# MD5133-A02-01.net
KiCad netlist of a schematic drawn in Altium Designer
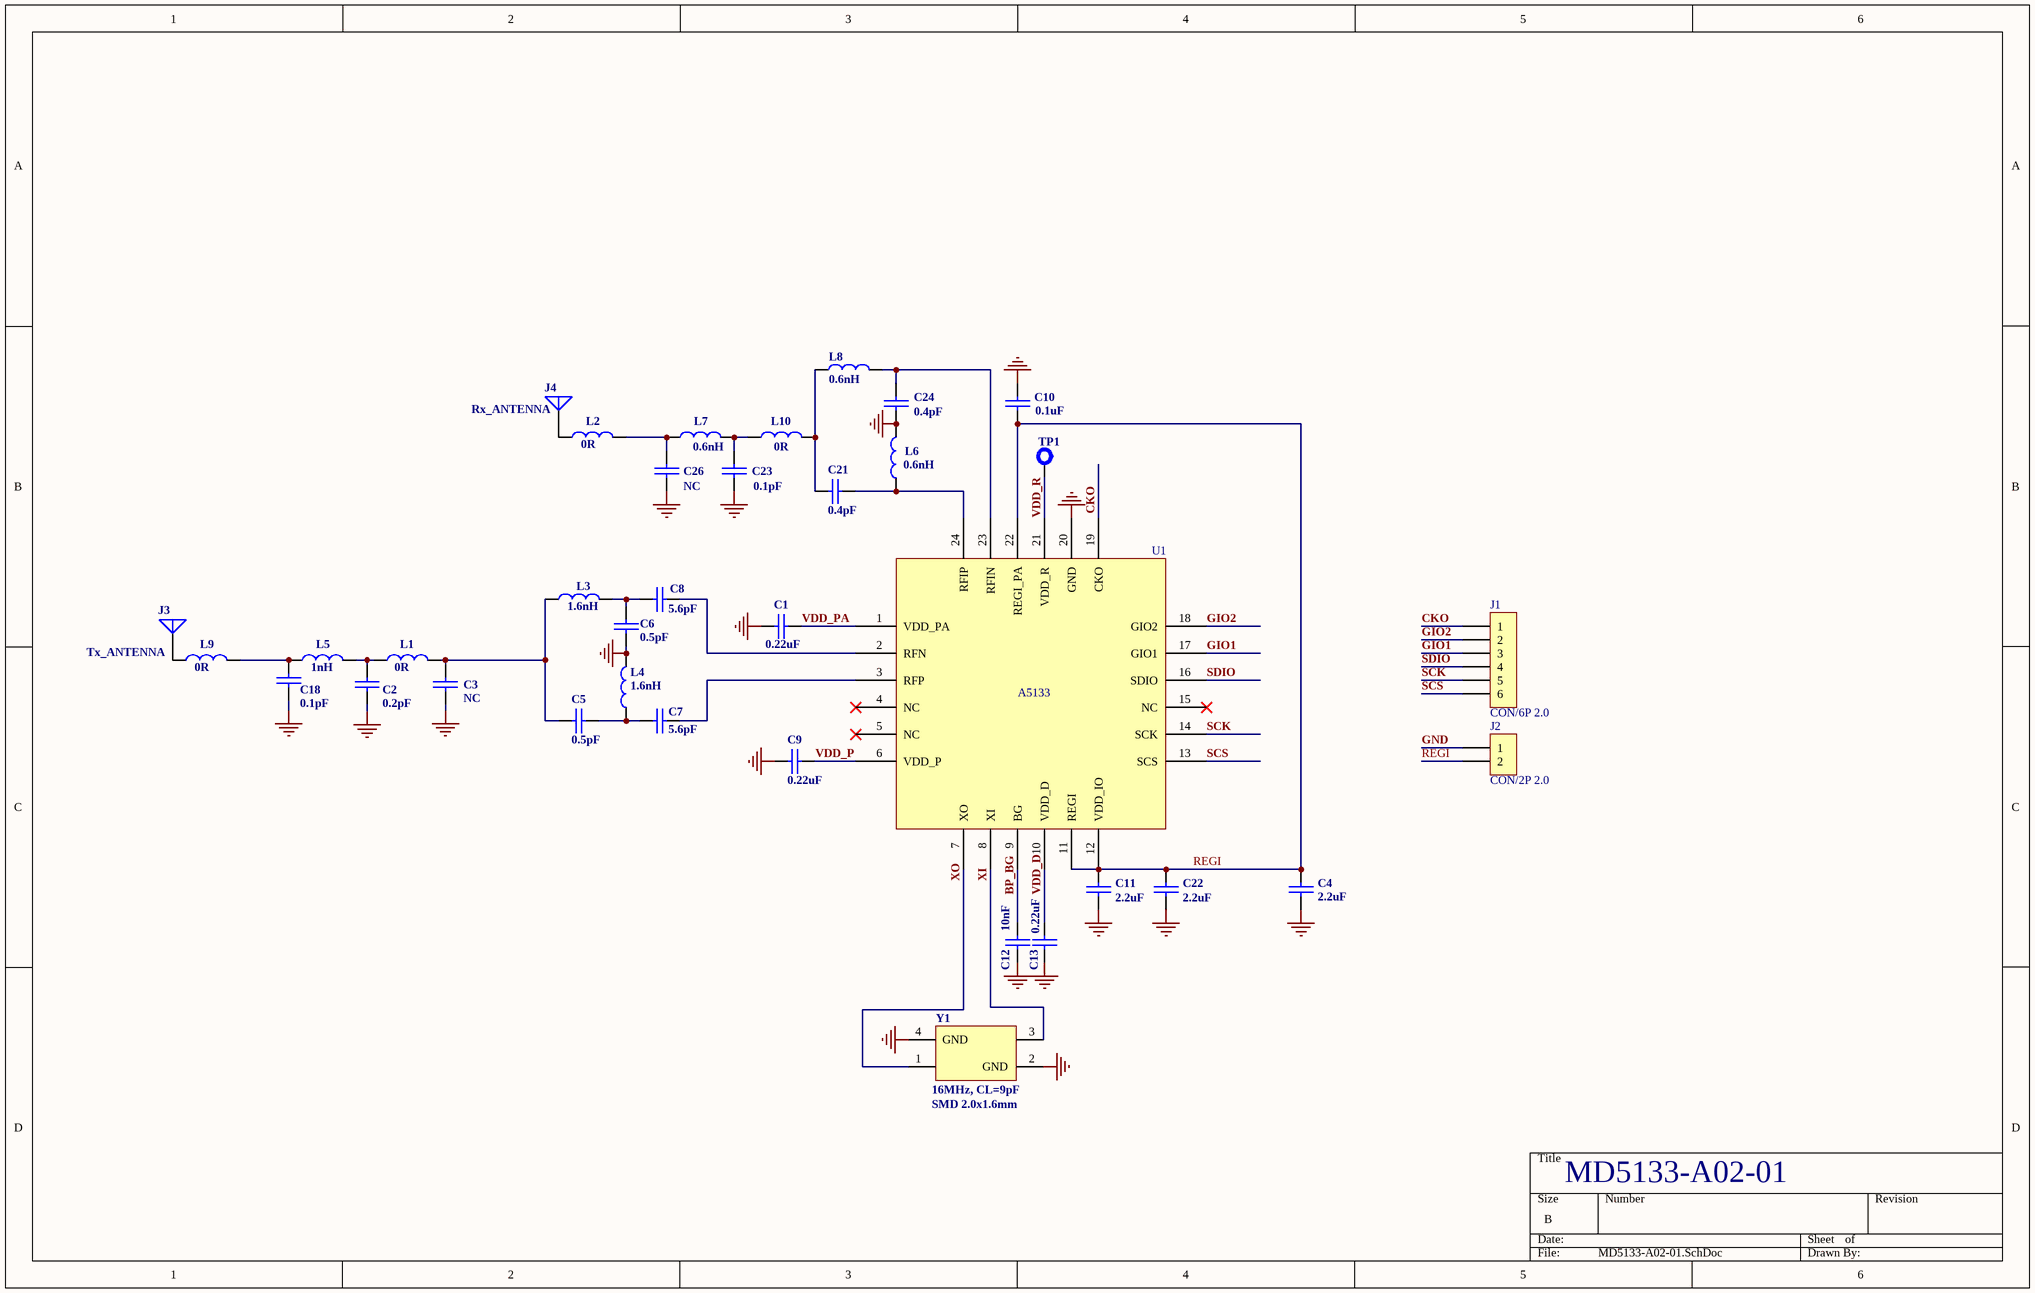
[diagram p0: MD5133-A02-01.SchDoc]

(export (version "E")
  (design (tool "Eeschema 10.0.6"))
  (components
    (comp (ref "C1") (value "0.22uF") (footprint "0402") (libsource (lib "*") (part "CAP")))
    (comp (ref "C2")
      (value "0.2pF")
      (footprint "0402-3")
      (description "Chip C")
      (libsource (lib "*") (part "C/0603"))
    )
    (comp (ref "C3")
      (value "NC")
      (footprint "0402-3")
      (description "Chip C")
      (libsource (lib "*") (part "C/0603"))
    )
    (comp (ref "C4") (value "2.2uF") (footprint "0402") (libsource (lib "*") (part "CAP")))
    (comp (ref "C5")
      (value "0.5pF")
      (footprint "0402-3")
      (description "Chip C")
      (libsource (lib "*") (part "C/0603"))
    )
    (comp (ref "C6")
      (value "0.5pF")
      (footprint "0402-3")
      (description "Chip C")
      (libsource (lib "*") (part "C/0603"))
    )
    (comp (ref "C7")
      (value "5.6pF")
      (footprint "0402-3")
      (description "Chip C")
      (libsource (lib "*") (part "C/0603"))
    )
    (comp (ref "C8")
      (value "5.6pF")
      (footprint "0402-3")
      (description "Chip C")
      (libsource (lib "*") (part "C/0603"))
    )
    (comp (ref "C9") (value "0.22uF") (footprint "0402") (libsource (lib "*") (part "CAP")))
    (comp (ref "C10")
      (value "0.1uF")
      (footprint "0402")
      (description "Chip C")
      (libsource (lib "*") (part "C/0603"))
    )
    (comp (ref "C11") (value "2.2uF") (footprint "0402") (libsource (lib "*") (part "CAP")))
    (comp (ref "C12") (value "10nF") (footprint "0402") (libsource (lib "*") (part "CAP")))
    (comp (ref "C13") (value "0.22uF") (footprint "0402") (libsource (lib "*") (part "CAP")))
    (comp (ref "C18")
      (value "0.1pF")
      (footprint "0402-3")
      (description "Chip C")
      (libsource (lib "*") (part "C/0603"))
    )
    (comp (ref "C21")
      (value "0.4pF")
      (footprint "0402-3")
      (description "Chip C")
      (libsource (lib "*") (part "C/0603"))
    )
    (comp (ref "C22") (value "2.2uF") (footprint "0402") (libsource (lib "*") (part "CAP")))
    (comp (ref "C23")
      (value "0.1pF")
      (footprint "0402-3")
      (description "Chip C")
      (libsource (lib "*") (part "C/0603"))
    )
    (comp (ref "C24")
      (value "0.4pF")
      (footprint "0402-3")
      (description "Chip C")
      (libsource (lib "*") (part "C/0603"))
    )
    (comp (ref "C26")
      (value "NC")
      (footprint "0402-3")
      (description "Chip C")
      (libsource (lib "*") (part "C/0603"))
    )
    (comp (ref "J1")
      (value "CON/6P 2.0")
      (footprint "HDR6_2.0")
      (description "Hole 36mil")
      (libsource (lib "AMICCOM-S") (part "CON/6P 2.0"))
    )
    (comp (ref "J2")
      (value "CON/2P 2.0")
      (footprint "HDR2_2.0")
      (description "Hole 36mil")
      (libsource (lib "AMICCOM-S") (part "CON/2P 2.0"))
    )
    (comp (ref "J3")
      (value "Tx_ANTENNA")
      (footprint "ANT3_5.8G-A1011")
      (libsource (lib "AMICCOM-S") (part "ANTENNA"))
    )
    (comp (ref "J4")
      (value "Rx_ANTENNA")
      (footprint "ANT3_5.8G-A1011")
      (libsource (lib "AMICCOM-S") (part "ANTENNA"))
    )
    (comp (ref "L1") (value "0R") (footprint "0402-3") (libsource (lib "") (part "L/0603_4")))
    (comp (ref "L2") (value "0R") (footprint "0402-3") (libsource (lib "") (part "L/0603_3")))
    (comp (ref "L3") (value "1.6nH") (footprint "0402-3") (libsource (lib "") (part "L/0603_4")))
    (comp (ref "L4") (value "1.6nH") (footprint "0402-3") (libsource (lib "") (part "L/0603_2")))
    (comp (ref "L5") (value "1nH") (footprint "0402-3") (libsource (lib "") (part "L/0603_3")))
    (comp (ref "L6") (value "0.6nH") (footprint "0402-3") (libsource (lib "") (part "L/0603_1")))
    (comp (ref "L7") (value "0.6nH") (footprint "0402-3") (libsource (lib "*") (part "L/0603")))
    (comp (ref "L8") (value "0.6nH") (footprint "0402-3") (libsource (lib "*") (part "L/0603")))
    (comp (ref "L9") (value "0R") (footprint "0402-3") (libsource (lib "") (part "L/0603_3")))
    (comp (ref "L10") (value "0R") (footprint "0402-3") (libsource (lib "*") (part "L/0603")))
    (comp (ref "TP1") (value "TP") (footprint "PAD - SMD") (libsource (lib "AMICCOM-S") (part "TP")))
    (comp (ref "U1")
      (value "A5133_U02_Q4P24")
      (footprint "QFN 4*4 24L_A7190")
      (libsource (lib "AMICCOM-S") (part "A5133_U02_Q4P24"))
    )
    (comp (ref "Y1")
      (value "16MHz, CL=9pF")
      (footprint "XTAL_2.0 *1.6")
      (description "12.8MHz , 20P")
      (libsource (lib "AMICCOM-S") (part "CRYSTAL/5*3.2"))
    )
  )
  (nets
    (net (code "1") (name "/BP_BG") (class "Default")
      (node (ref "C12") (pin "2") (pinfunction "2_2") (pintype "passive"))
      (node (ref "U1") (pin "9") (pinfunction "BG_9") (pintype "passive"))
    )
    (net (code "2") (name "/CKO") (class "Default")
      (node (ref "J1") (pin "1") (pinfunction "1_1") (pintype "passive"))
      (node (ref "U1") (pin "19") (pinfunction "CKO_19") (pintype "passive"))
    )
    (net (code "3") (name "/GIO1") (class "Default")
      (node (ref "J1") (pin "3") (pinfunction "3_3") (pintype "passive"))
      (node (ref "U1") (pin "17") (pinfunction "GIO1_17") (pintype "passive"))
    )
    (net (code "4") (name "/GIO2") (class "Default")
      (node (ref "J1") (pin "2") (pinfunction "2_2") (pintype "passive"))
      (node (ref "U1") (pin "18") (pinfunction "GIO2_18") (pintype "passive"))
    )
    (net (code "5") (name "/REGI") (class "Default")
      (node (ref "C10") (pin "1") (pinfunction "1_1") (pintype "passive"))
      (node (ref "C11") (pin "2") (pinfunction "2_2") (pintype "passive"))
      (node (ref "C22") (pin "2") (pinfunction "2_2") (pintype "passive"))
      (node (ref "C4") (pin "2") (pinfunction "2_2") (pintype "passive"))
      (node (ref "J2") (pin "2") (pinfunction "2_2") (pintype "passive"))
      (node (ref "U1") (pin "11") (pinfunction "REGI_11") (pintype "passive"))
      (node (ref "U1") (pin "12") (pinfunction "VDD_IO_12") (pintype "passive"))
      (node (ref "U1") (pin "22") (pinfunction "REGI_PA_22") (pintype "passive"))
    )
    (net (code "6") (name "/SCK") (class "Default")
      (node (ref "J1") (pin "5") (pinfunction "5_5") (pintype "passive"))
      (node (ref "U1") (pin "14") (pinfunction "SCK_14") (pintype "passive"))
    )
    (net (code "7") (name "/SCS") (class "Default")
      (node (ref "J1") (pin "6") (pinfunction "6_6") (pintype "passive"))
      (node (ref "U1") (pin "13") (pinfunction "SCS_13") (pintype "passive"))
    )
    (net (code "8") (name "/SDIO") (class "Default")
      (node (ref "J1") (pin "4") (pinfunction "4_4") (pintype "passive"))
      (node (ref "U1") (pin "16") (pinfunction "SDIO_16") (pintype "passive"))
    )
    (net (code "9") (name "/VDD_D") (class "Default")
      (node (ref "C13") (pin "2") (pinfunction "2_2") (pintype "passive"))
      (node (ref "U1") (pin "10") (pinfunction "VDD_D_10") (pintype "passive"))
    )
    (net (code "10") (name "/VDD_P") (class "Default")
      (node (ref "C9") (pin "1") (pinfunction "1_1") (pintype "passive"))
      (node (ref "U1") (pin "6") (pinfunction "VDD_P_6") (pintype "passive"))
    )
    (net (code "11") (name "/VDD_PA") (class "Default")
      (node (ref "C1") (pin "2") (pinfunction "2_2") (pintype "passive"))
      (node (ref "U1") (pin "1") (pinfunction "VDD_PA_1") (pintype "passive"))
    )
    (net (code "12") (name "/VDD_R") (class "Default")
      (node (ref "TP1") (pin "1") (pinfunction "1_1") (pintype "passive"))
      (node (ref "U1") (pin "21") (pinfunction "VDD_R_21") (pintype "passive"))
    )
    (net (code "13") (name "/XI") (class "Default")
      (node (ref "U1") (pin "8") (pinfunction "XI_8") (pintype "passive"))
      (node (ref "Y1") (pin "3") (pintype "passive"))
    )
    (net (code "14") (name "/XO") (class "Default")
      (node (ref "U1") (pin "7") (pinfunction "XO_7") (pintype "passive"))
      (node (ref "Y1") (pin "1") (pintype "passive"))
    )
    (net (code "15") (name "GND") (class "Default")
      (node (ref "C1") (pin "1") (pinfunction "1_1") (pintype "passive"))
      (node (ref "C10") (pin "2") (pinfunction "2_2") (pintype "passive"))
      (node (ref "C11") (pin "1") (pinfunction "1_1") (pintype "passive"))
      (node (ref "C12") (pin "1") (pinfunction "1_1") (pintype "passive"))
      (node (ref "C13") (pin "1") (pinfunction "1_1") (pintype "passive"))
      (node (ref "C18") (pin "2") (pinfunction "2_2") (pintype "passive"))
      (node (ref "C2") (pin "2") (pinfunction "2_2") (pintype "passive"))
      (node (ref "C22") (pin "1") (pinfunction "1_1") (pintype "passive"))
      (node (ref "C23") (pin "1") (pinfunction "1_1") (pintype "passive"))
      (node (ref "C24") (pin "1") (pinfunction "1_1") (pintype "passive"))
      (node (ref "C26") (pin "1") (pinfunction "1_1") (pintype "passive"))
      (node (ref "C3") (pin "2") (pinfunction "2_2") (pintype "passive"))
      (node (ref "C4") (pin "1") (pinfunction "1_1") (pintype "passive"))
      (node (ref "C6") (pin "2") (pinfunction "2_2") (pintype "passive"))
      (node (ref "C9") (pin "2") (pinfunction "2_2") (pintype "passive"))
      (node (ref "J2") (pin "1") (pinfunction "1_1") (pintype "passive"))
      (node (ref "L4") (pin "2") (pinfunction "2_2") (pintype "passive"))
      (node (ref "L6") (pin "1") (pinfunction "1_1") (pintype "passive"))
      (node (ref "U1") (pin "20") (pinfunction "GND_20") (pintype "passive"))
      (node (ref "Y1") (pin "2") (pinfunction "GND_2") (pintype "passive"))
      (node (ref "Y1") (pin "4") (pinfunction "GND_4") (pintype "passive"))
    )
    (net (code "16") (name "Net-(C2-Pad1)") (class "Default")
      (node (ref "C2") (pin "1") (pinfunction "1_1") (pintype "passive"))
      (node (ref "L1") (pin "1") (pinfunction "1_1") (pintype "passive"))
      (node (ref "L5") (pin "1") (pinfunction "1_1") (pintype "passive"))
    )
    (net (code "17") (name "Net-(C3-Pad1)") (class "Default")
      (node (ref "C3") (pin "1") (pinfunction "1_1") (pintype "passive"))
      (node (ref "C5") (pin "2") (pinfunction "2_2") (pintype "passive"))
      (node (ref "L1") (pin "2") (pinfunction "2_2") (pintype "passive"))
      (node (ref "L3") (pin "1") (pinfunction "1_1") (pintype "passive"))
    )
    (net (code "18") (name "Net-(C5-Pad1)") (class "Default")
      (node (ref "C5") (pin "1") (pinfunction "1_1") (pintype "passive"))
      (node (ref "C7") (pin "1") (pinfunction "1_1") (pintype "passive"))
      (node (ref "L4") (pin "1") (pinfunction "1_1") (pintype "passive"))
    )
    (net (code "19") (name "Net-(C6-Pad1)") (class "Default")
      (node (ref "C6") (pin "1") (pinfunction "1_1") (pintype "passive"))
      (node (ref "C8") (pin "1") (pinfunction "1_1") (pintype "passive"))
      (node (ref "L3") (pin "2") (pinfunction "2_2") (pintype "passive"))
    )
    (net (code "20") (name "Net-(C18-Pad1)") (class "Default")
      (node (ref "C18") (pin "1") (pinfunction "1_1") (pintype "passive"))
      (node (ref "L5") (pin "2") (pinfunction "2_2") (pintype "passive"))
      (node (ref "L9") (pin "1") (pinfunction "1_1") (pintype "passive"))
    )
    (net (code "21") (name "Net-(C21-Pad2)") (class "Default")
      (node (ref "C21") (pin "2") (pinfunction "2_2") (pintype "passive"))
      (node (ref "L10") (pin "1") (pinfunction "1_1") (pintype "passive"))
      (node (ref "L8") (pin "2") (pinfunction "2_2") (pintype "passive"))
    )
    (net (code "22") (name "Net-(C23-Pad2)") (class "Default")
      (node (ref "C23") (pin "2") (pinfunction "2_2") (pintype "passive"))
      (node (ref "L10") (pin "2") (pinfunction "2_2") (pintype "passive"))
      (node (ref "L7") (pin "1") (pinfunction "1_1") (pintype "passive"))
    )
    (net (code "23") (name "Net-(C26-Pad2)") (class "Default")
      (node (ref "C26") (pin "2") (pinfunction "2_2") (pintype "passive"))
      (node (ref "L2") (pin "1") (pinfunction "1_1") (pintype "passive"))
      (node (ref "L7") (pin "2") (pinfunction "2_2") (pintype "passive"))
    )
    (net (code "24") (name "Net-(J3-A)") (class "Default")
      (node (ref "J3") (pin "1") (pinfunction "A_1") (pintype "passive"))
      (node (ref "L9") (pin "2") (pinfunction "2_2") (pintype "passive"))
    )
    (net (code "25") (name "Net-(J4-A)") (class "Default")
      (node (ref "J4") (pin "1") (pinfunction "A_1") (pintype "passive"))
      (node (ref "L2") (pin "2") (pinfunction "2_2") (pintype "passive"))
    )
    (net (code "26") (name "Net-(U1-RFIN)") (class "Default")
      (node (ref "C24") (pin "2") (pinfunction "2_2") (pintype "passive"))
      (node (ref "L8") (pin "1") (pinfunction "1_1") (pintype "passive"))
      (node (ref "U1") (pin "23") (pinfunction "RFIN_23") (pintype "passive"))
    )
    (net (code "27") (name "Net-(U1-RFIP)") (class "Default")
      (node (ref "C21") (pin "1") (pinfunction "1_1") (pintype "passive"))
      (node (ref "L6") (pin "2") (pinfunction "2_2") (pintype "passive"))
      (node (ref "U1") (pin "24") (pinfunction "RFIP_24") (pintype "passive"))
    )
    (net (code "28") (name "Net-(U1-RFN)") (class "Default")
      (node (ref "C8") (pin "2") (pinfunction "2_2") (pintype "passive"))
      (node (ref "U1") (pin "2") (pinfunction "RFN_2") (pintype "passive"))
    )
    (net (code "29") (name "Net-(U1-RFP)") (class "Default")
      (node (ref "C7") (pin "2") (pinfunction "2_2") (pintype "passive"))
      (node (ref "U1") (pin "3") (pinfunction "RFP_3") (pintype "passive"))
    )
    (net (code "30") (name "unconnected-(U1-NC-Pad4)") (class "Default")
      (node (ref "U1") (pin "4") (pinfunction "NC_4") (pintype "passive+no_connect"))
    )
    (net (code "31") (name "unconnected-(U1-NC-Pad5)") (class "Default")
      (node (ref "U1") (pin "5") (pinfunction "NC_5") (pintype "passive+no_connect"))
    )
    (net (code "32") (name "unconnected-(U1-NC-Pad15)") (class "Default")
      (node (ref "U1") (pin "15") (pinfunction "NC_15") (pintype "passive+no_connect"))
    )
  )
)
